# STORAGE.net
KiCad netlist of a schematic drawn in Altium Designer
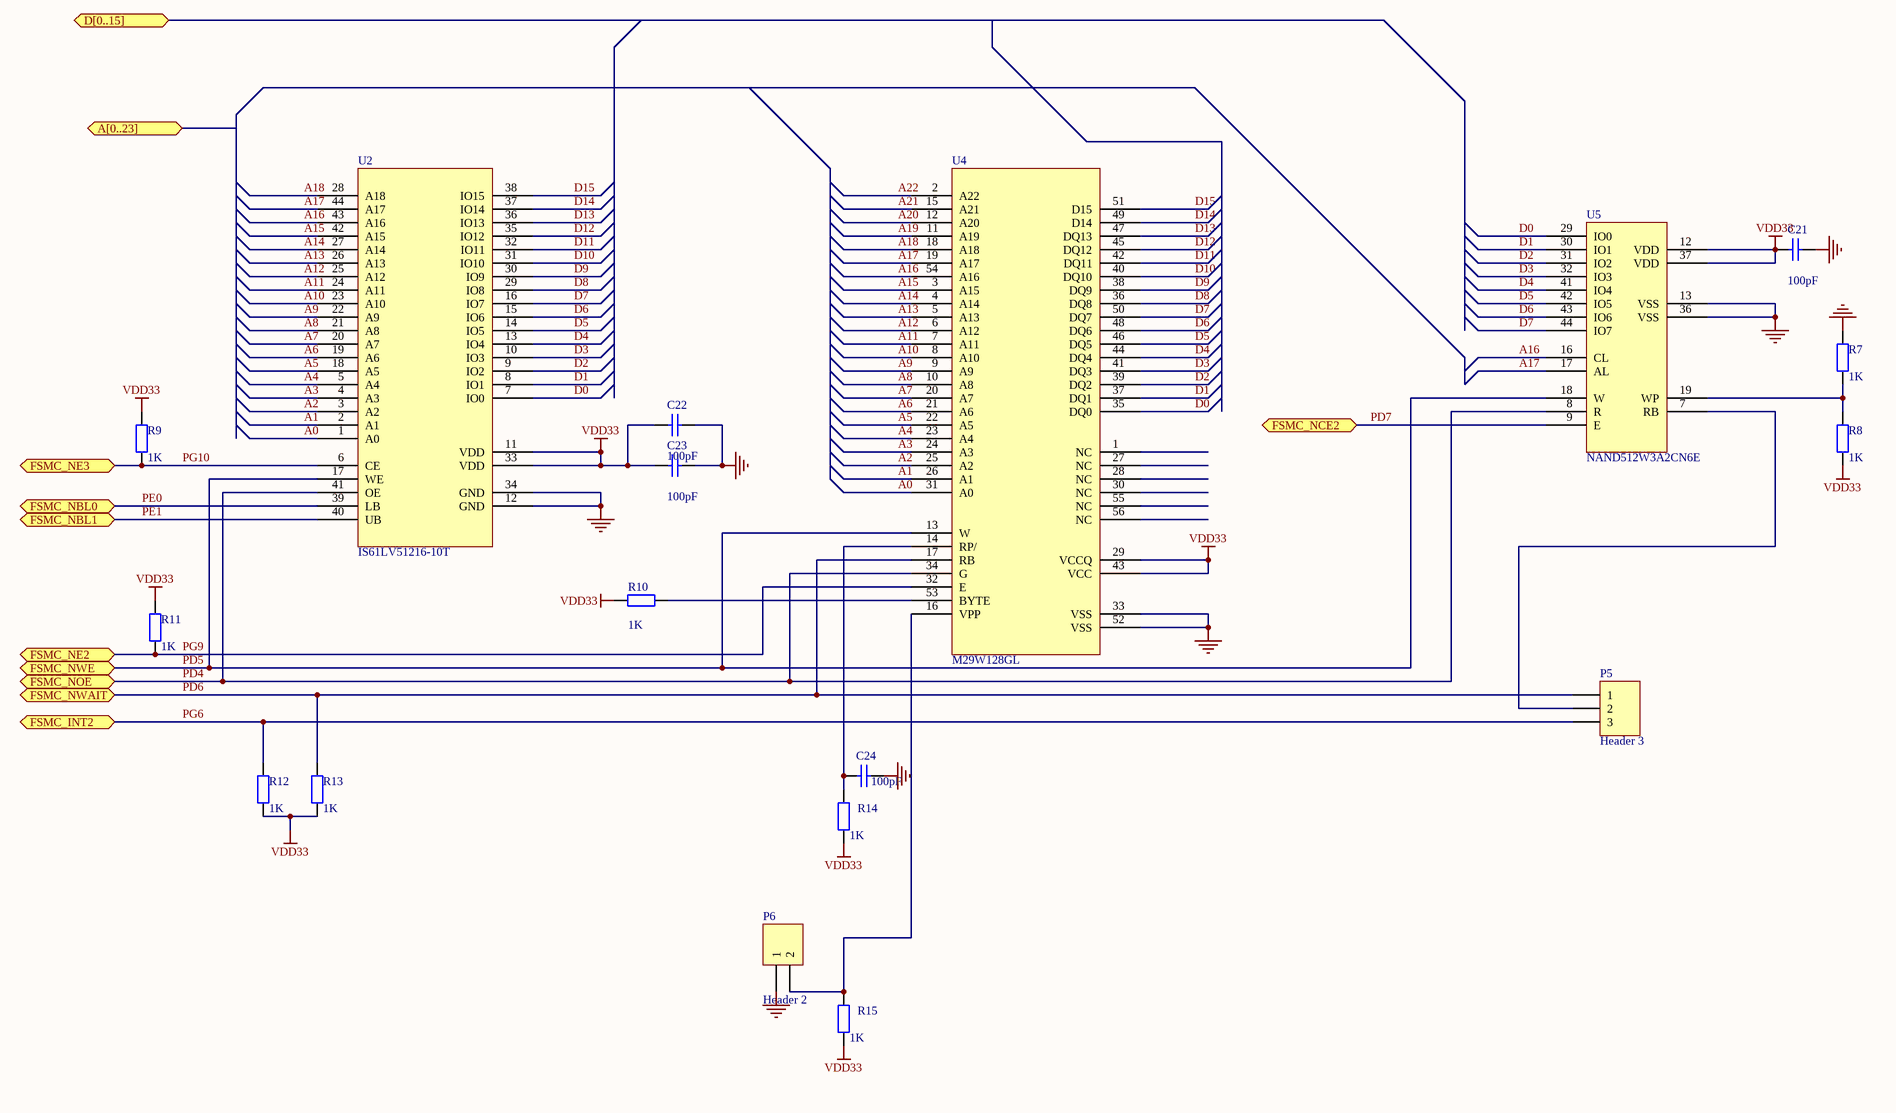
[diagram p0: STORAGE.SchDoc]

(export (version "E")
  (design (tool "Eeschema 10.0.6"))
  (components
    (comp (ref "C21")
      (value "100pF")
      (footprint "0805")
      (description "Capacitor")
      (fields (field (name "Comment") "Cap") (field (name "PUBLISHER") "Altium Limited"))
      (libsource (lib "Miscellaneous Devices") (part "Cap"))
    )
    (comp (ref "C22")
      (value "100pF")
      (footprint "0805")
      (description "Capacitor")
      (fields (field (name "Comment") "Cap") (field (name "PUBLISHER") "Altium Limited"))
      (libsource (lib "Miscellaneous Devices") (part "Cap"))
    )
    (comp (ref "C23")
      (value "100pF")
      (footprint "0805")
      (description "Capacitor")
      (fields (field (name "Comment") "Cap") (field (name "PUBLISHER") "Altium Limited"))
      (libsource (lib "Miscellaneous Devices") (part "Cap"))
    )
    (comp (ref "C24")
      (value "100pF")
      (footprint "0805")
      (description "Capacitor")
      (fields (field (name "Comment") "Cap") (field (name "PUBLISHER") "Altium Limited"))
      (libsource (lib "Miscellaneous Devices") (part "Cap"))
    )
    (comp (ref "P5")
      (value "Header 3")
      (footprint "HDR1X3")
      (description "Header, 3-Pin")
      (fields (field (name "PUBLISHER") "Altium Limited"))
      (libsource (lib "Miscellaneous Connectors") (part "Header 3"))
    )
    (comp (ref "P6")
      (value "Header 2")
      (footprint "HDR1X2")
      (description "Header, 2-Pin")
      (fields (field (name "PUBLISHER") "Altium Limited"))
      (libsource (lib "Miscellaneous Connectors") (part "Header 2"))
    )
    (comp (ref "R7")
      (value "1K")
      (footprint "0805")
      (description "Resistor")
      (fields (field (name "Comment") "Res2") (field (name "PUBLISHER") "Altium Limited"))
      (libsource (lib "") (part "Res2_2"))
    )
    (comp (ref "R8")
      (value "1K")
      (footprint "0805")
      (description "Resistor")
      (fields (field (name "Comment") "Res2") (field (name "PUBLISHER") "Altium Limited"))
      (libsource (lib "") (part "Res2_2"))
    )
    (comp (ref "R9")
      (value "1K")
      (footprint "0805")
      (description "Resistor")
      (fields (field (name "Comment") "Res2") (field (name "PUBLISHER") "Altium Limited"))
      (libsource (lib "") (part "Res2_2"))
    )
    (comp (ref "R10")
      (value "1K")
      (footprint "0805")
      (description "Resistor")
      (fields (field (name "Comment") "Res2") (field (name "PUBLISHER") "Altium Limited"))
      (libsource (lib "") (part "Res2_1"))
    )
    (comp (ref "R11")
      (value "1K")
      (footprint "0805")
      (description "Resistor")
      (fields (field (name "Comment") "Res2") (field (name "PUBLISHER") "Altium Limited"))
      (libsource (lib "") (part "Res2_2"))
    )
    (comp (ref "R12")
      (value "1K")
      (footprint "0805")
      (description "Resistor")
      (fields (field (name "Comment") "Res2") (field (name "PUBLISHER") "Altium Limited"))
      (libsource (lib "Miscellaneous Devices") (part "Res2"))
    )
    (comp (ref "R13")
      (value "1K")
      (footprint "0805")
      (description "Resistor")
      (fields (field (name "Comment") "Res2") (field (name "PUBLISHER") "Altium Limited"))
      (libsource (lib "") (part "Res2_2"))
    )
    (comp (ref "R14")
      (value "1K")
      (footprint "0805")
      (description "Resistor")
      (fields (field (name "Comment") "Res2") (field (name "PUBLISHER") "Altium Limited"))
      (libsource (lib "") (part "Res2_2"))
    )
    (comp (ref "R15")
      (value "1K")
      (footprint "0805")
      (description "Resistor")
      (fields (field (name "Comment") "Res2") (field (name "PUBLISHER") "Altium Limited"))
      (libsource (lib "") (part "Res2_2"))
    )
    (comp (ref "U2")
      (value "IS61LV51216-10T")
      (footprint "TSOP44")
      (libsource (lib "Schlib1") (part "IS61LV51216-10T"))
    )
    (comp (ref "U4") (value "M29W128GL") (footprint "TSOP56") (libsource (lib "Schlib1") (part "M29W128GL")))
    (comp (ref "U5")
      (value "NAND512W3A2CN6E")
      (footprint "TSOP48")
      (libsource (lib "Schlib1") (part "NAND512W3A2CN6E"))
    )
  )
  (nets
    (net (code "2") (name "/A0") (class "Default")
      (node (ref "U2") (pin "1") (pinfunction "A0_1") (pintype "passive"))
      (node (ref "U4") (pin "31") (pinfunction "A0_31") (pintype "passive"))
    )
    (net (code "3") (name "/A1") (class "Default")
      (node (ref "U2") (pin "2") (pinfunction "A1_2") (pintype "passive"))
      (node (ref "U4") (pin "26") (pinfunction "A1_26") (pintype "passive"))
    )
    (net (code "4") (name "/A2") (class "Default")
      (node (ref "U2") (pin "3") (pinfunction "A2_3") (pintype "passive"))
      (node (ref "U4") (pin "25") (pinfunction "A2_25") (pintype "passive"))
    )
    (net (code "5") (name "/A3") (class "Default")
      (node (ref "U2") (pin "4") (pinfunction "A3_4") (pintype "passive"))
      (node (ref "U4") (pin "24") (pinfunction "A3_24") (pintype "passive"))
    )
    (net (code "6") (name "/A4") (class "Default")
      (node (ref "U2") (pin "5") (pinfunction "A4_5") (pintype "passive"))
      (node (ref "U4") (pin "23") (pinfunction "A4_23") (pintype "passive"))
    )
    (net (code "7") (name "/A5") (class "Default")
      (node (ref "U2") (pin "18") (pinfunction "A5_18") (pintype "passive"))
      (node (ref "U4") (pin "22") (pinfunction "A5_22") (pintype "passive"))
    )
    (net (code "8") (name "/A6") (class "Default")
      (node (ref "U2") (pin "19") (pinfunction "A6_19") (pintype "passive"))
      (node (ref "U4") (pin "21") (pinfunction "A6_21") (pintype "passive"))
    )
    (net (code "9") (name "/A7") (class "Default")
      (node (ref "U2") (pin "20") (pinfunction "A7_20") (pintype "passive"))
      (node (ref "U4") (pin "20") (pinfunction "A7_20") (pintype "passive"))
    )
    (net (code "10") (name "/A8") (class "Default")
      (node (ref "U2") (pin "21") (pinfunction "A8_21") (pintype "passive"))
      (node (ref "U4") (pin "10") (pinfunction "A8_10") (pintype "passive"))
    )
    (net (code "11") (name "/A9") (class "Default")
      (node (ref "U2") (pin "22") (pinfunction "A9_22") (pintype "passive"))
      (node (ref "U4") (pin "9") (pinfunction "A9_9") (pintype "passive"))
    )
    (net (code "12") (name "/A10") (class "Default")
      (node (ref "U2") (pin "23") (pinfunction "A10_23") (pintype "passive"))
      (node (ref "U4") (pin "8") (pinfunction "A10_8") (pintype "passive"))
    )
    (net (code "13") (name "/A11") (class "Default")
      (node (ref "U2") (pin "24") (pinfunction "A11_24") (pintype "passive"))
      (node (ref "U4") (pin "7") (pinfunction "A11_7") (pintype "passive"))
    )
    (net (code "14") (name "/A12") (class "Default")
      (node (ref "U2") (pin "25") (pinfunction "A12_25") (pintype "passive"))
      (node (ref "U4") (pin "6") (pinfunction "A12_6") (pintype "passive"))
    )
    (net (code "15") (name "/A13") (class "Default")
      (node (ref "U2") (pin "26") (pinfunction "A13_26") (pintype "passive"))
      (node (ref "U4") (pin "5") (pinfunction "A13_5") (pintype "passive"))
    )
    (net (code "16") (name "/A14") (class "Default")
      (node (ref "U2") (pin "27") (pinfunction "A14_27") (pintype "passive"))
      (node (ref "U4") (pin "4") (pinfunction "A14_4") (pintype "passive"))
    )
    (net (code "17") (name "/A15") (class "Default")
      (node (ref "U2") (pin "42") (pinfunction "A15_42") (pintype "passive"))
      (node (ref "U4") (pin "3") (pinfunction "A15_3") (pintype "passive"))
    )
    (net (code "18") (name "/A16") (class "Default")
      (node (ref "U2") (pin "43") (pinfunction "A16_43") (pintype "passive"))
      (node (ref "U4") (pin "54") (pinfunction "A16_54") (pintype "passive"))
      (node (ref "U5") (pin "16") (pinfunction "CL_16") (pintype "passive"))
    )
    (net (code "19") (name "/A17") (class "Default")
      (node (ref "U2") (pin "44") (pinfunction "A17_44") (pintype "passive"))
      (node (ref "U4") (pin "19") (pinfunction "A17_19") (pintype "passive"))
      (node (ref "U5") (pin "17") (pinfunction "AL_17") (pintype "passive"))
    )
    (net (code "20") (name "/A18") (class "Default")
      (node (ref "U2") (pin "28") (pinfunction "A18_28") (pintype "passive"))
      (node (ref "U4") (pin "18") (pinfunction "A18_18") (pintype "passive"))
    )
    (net (code "21") (name "/A19") (class "Default")
      (node (ref "U4") (pin "11") (pinfunction "A19_11") (pintype "passive"))
    )
    (net (code "22") (name "/A20") (class "Default")
      (node (ref "U4") (pin "12") (pinfunction "A20_12") (pintype "passive"))
    )
    (net (code "23") (name "/A21") (class "Default")
      (node (ref "U4") (pin "15") (pinfunction "A21_15") (pintype "passive"))
    )
    (net (code "24") (name "/A22") (class "Default")
      (node (ref "U4") (pin "2") (pinfunction "A22_2") (pintype "passive"))
    )
    (net (code "26") (name "/D0") (class "Default")
      (node (ref "U2") (pin "7") (pinfunction "IO0_7") (pintype "passive"))
      (node (ref "U4") (pin "35") (pinfunction "DQ0_35") (pintype "passive"))
      (node (ref "U5") (pin "29") (pinfunction "IO0_29") (pintype "passive"))
    )
    (net (code "27") (name "/D1") (class "Default")
      (node (ref "U2") (pin "8") (pinfunction "IO1_8") (pintype "passive"))
      (node (ref "U4") (pin "37") (pinfunction "DQ1_37") (pintype "passive"))
      (node (ref "U5") (pin "30") (pinfunction "IO1_30") (pintype "passive"))
    )
    (net (code "28") (name "/D2") (class "Default")
      (node (ref "U2") (pin "9") (pinfunction "IO2_9") (pintype "passive"))
      (node (ref "U4") (pin "39") (pinfunction "DQ2_39") (pintype "passive"))
      (node (ref "U5") (pin "31") (pinfunction "IO2_31") (pintype "passive"))
    )
    (net (code "29") (name "/D3") (class "Default")
      (node (ref "U2") (pin "10") (pinfunction "IO3_10") (pintype "passive"))
      (node (ref "U4") (pin "41") (pinfunction "DQ3_41") (pintype "passive"))
      (node (ref "U5") (pin "32") (pinfunction "IO3_32") (pintype "passive"))
    )
    (net (code "30") (name "/D4") (class "Default")
      (node (ref "U2") (pin "13") (pinfunction "IO4_13") (pintype "passive"))
      (node (ref "U4") (pin "44") (pinfunction "DQ4_44") (pintype "passive"))
      (node (ref "U5") (pin "41") (pinfunction "IO4_41") (pintype "passive"))
    )
    (net (code "31") (name "/D5") (class "Default")
      (node (ref "U2") (pin "14") (pinfunction "IO5_14") (pintype "passive"))
      (node (ref "U4") (pin "46") (pinfunction "DQ5_46") (pintype "passive"))
      (node (ref "U5") (pin "42") (pinfunction "IO5_42") (pintype "passive"))
    )
    (net (code "32") (name "/D6") (class "Default")
      (node (ref "U2") (pin "15") (pinfunction "IO6_15") (pintype "passive"))
      (node (ref "U4") (pin "48") (pinfunction "DQ6_48") (pintype "passive"))
      (node (ref "U5") (pin "43") (pinfunction "IO6_43") (pintype "passive"))
    )
    (net (code "33") (name "/D7") (class "Default")
      (node (ref "U2") (pin "16") (pinfunction "IO7_16") (pintype "passive"))
      (node (ref "U4") (pin "50") (pinfunction "DQ7_50") (pintype "passive"))
      (node (ref "U5") (pin "44") (pinfunction "IO7_44") (pintype "passive"))
    )
    (net (code "34") (name "/D8") (class "Default")
      (node (ref "U2") (pin "29") (pinfunction "IO8_29") (pintype "passive"))
      (node (ref "U4") (pin "36") (pinfunction "DQ8_36") (pintype "passive"))
    )
    (net (code "35") (name "/D9") (class "Default")
      (node (ref "U2") (pin "30") (pinfunction "IO9_30") (pintype "passive"))
      (node (ref "U4") (pin "38") (pinfunction "DQ9_38") (pintype "passive"))
    )
    (net (code "36") (name "/D10") (class "Default")
      (node (ref "U2") (pin "31") (pinfunction "IO10_31") (pintype "passive"))
      (node (ref "U4") (pin "40") (pinfunction "DQ10_40") (pintype "passive"))
    )
    (net (code "37") (name "/D11") (class "Default")
      (node (ref "U2") (pin "32") (pinfunction "IO11_32") (pintype "passive"))
      (node (ref "U4") (pin "42") (pinfunction "DQ11_42") (pintype "passive"))
    )
    (net (code "38") (name "/D12") (class "Default")
      (node (ref "U2") (pin "35") (pinfunction "IO12_35") (pintype "passive"))
      (node (ref "U4") (pin "45") (pinfunction "DQ12_45") (pintype "passive"))
    )
    (net (code "39") (name "/D13") (class "Default")
      (node (ref "U2") (pin "36") (pinfunction "IO13_36") (pintype "passive"))
      (node (ref "U4") (pin "47") (pinfunction "DQ13_47") (pintype "passive"))
    )
    (net (code "40") (name "/D14") (class "Default")
      (node (ref "U2") (pin "37") (pinfunction "IO14_37") (pintype "passive"))
      (node (ref "U4") (pin "49") (pinfunction "D14_49") (pintype "passive"))
    )
    (net (code "41") (name "/D15") (class "Default")
      (node (ref "U2") (pin "38") (pinfunction "IO15_38") (pintype "passive"))
      (node (ref "U4") (pin "51") (pinfunction "D15_51") (pintype "passive"))
    )
    (net (code "43") (name "/PD4") (class "Default")
      (node (ref "U2") (pin "41") (pinfunction "OE_41") (pintype "passive"))
      (node (ref "U4") (pin "34") (pinfunction "G_34") (pintype "passive"))
      (node (ref "U5") (pin "8") (pinfunction "R_8") (pintype "passive"))
    )
    (net (code "44") (name "/PD5") (class "Default")
      (node (ref "U2") (pin "17") (pinfunction "WE_17") (pintype "passive"))
      (node (ref "U4") (pin "13") (pinfunction "W_13") (pintype "passive"))
      (node (ref "U5") (pin "18") (pinfunction "W_18") (pintype "passive"))
    )
    (net (code "45") (name "/PD6") (class "Default")
      (node (ref "P5") (pin "1") (pinfunction "1_1") (pintype "passive"))
      (node (ref "R13") (pin "2") (pinfunction "2_2") (pintype "passive"))
      (node (ref "U4") (pin "17") (pinfunction "RB_17") (pintype "passive"))
    )
    (net (code "46") (name "/PD7") (class "Default")
      (node (ref "U5") (pin "9") (pinfunction "E_9") (pintype "passive"))
    )
    (net (code "47") (name "/PE0") (class "Default")
      (node (ref "U2") (pin "39") (pinfunction "LB_39") (pintype "passive"))
    )
    (net (code "48") (name "/PE1") (class "Default")
      (node (ref "U2") (pin "40") (pinfunction "UB_40") (pintype "passive"))
    )
    (net (code "49") (name "/PG6") (class "Default")
      (node (ref "P5") (pin "3") (pinfunction "3_3") (pintype "passive"))
      (node (ref "R12") (pin "1") (pinfunction "1_1") (pintype "passive"))
    )
    (net (code "50") (name "/PG9") (class "Default")
      (node (ref "R11") (pin "1") (pinfunction "1_1") (pintype "passive"))
      (node (ref "U4") (pin "32") (pinfunction "E_32") (pintype "passive"))
    )
    (net (code "51") (name "/PG10") (class "Default")
      (node (ref "R9") (pin "1") (pinfunction "1_1") (pintype "passive"))
      (node (ref "U2") (pin "6") (pinfunction "CE_6") (pintype "passive"))
    )
    (net (code "52") (name "GND") (class "Default")
      (node (ref "C21") (pin "2") (pinfunction "2_2") (pintype "passive"))
      (node (ref "C22") (pin "2") (pinfunction "2_2") (pintype "passive"))
      (node (ref "C23") (pin "2") (pinfunction "2_2") (pintype "passive"))
      (node (ref "C24") (pin "2") (pinfunction "2_2") (pintype "passive"))
      (node (ref "P6") (pin "1") (pinfunction "1_1") (pintype "passive"))
      (node (ref "R7") (pin "2") (pinfunction "2_2") (pintype "passive"))
      (node (ref "U2") (pin "12") (pinfunction "GND_12") (pintype "passive"))
      (node (ref "U2") (pin "34") (pinfunction "GND_34") (pintype "passive"))
      (node (ref "U4") (pin "33") (pinfunction "VSS_33") (pintype "passive"))
      (node (ref "U4") (pin "52") (pinfunction "VSS_52") (pintype "passive"))
      (node (ref "U5") (pin "13") (pinfunction "VSS_13") (pintype "passive"))
      (node (ref "U5") (pin "36") (pinfunction "VSS_36") (pintype "passive"))
    )
    (net (code "53") (name "Net-(U4-BYTE)") (class "Default")
      (node (ref "R10") (pin "1") (pinfunction "1_1") (pintype "passive"))
      (node (ref "U4") (pin "53") (pinfunction "BYTE_53") (pintype "passive"))
    )
    (net (code "54") (name "Net-(U4-RP{slash})") (class "Default")
      (node (ref "C24") (pin "1") (pinfunction "1_1") (pintype "passive"))
      (node (ref "R14") (pin "2") (pinfunction "2_2") (pintype "passive"))
      (node (ref "U4") (pin "14") (pinfunction "RP/_14") (pintype "passive"))
    )
    (net (code "55") (name "Net-(U4-VPP)") (class "Default")
      (node (ref "P6") (pin "2") (pinfunction "2_2") (pintype "passive"))
      (node (ref "R15") (pin "2") (pinfunction "2_2") (pintype "passive"))
      (node (ref "U4") (pin "16") (pinfunction "VPP_16") (pintype "passive"))
    )
    (net (code "56") (name "Net-(U5-RB)") (class "Default")
      (node (ref "P5") (pin "2") (pinfunction "2_2") (pintype "passive"))
      (node (ref "U5") (pin "7") (pinfunction "RB_7") (pintype "passive"))
    )
    (net (code "57") (name "Net-(U5-WP)") (class "Default")
      (node (ref "R7") (pin "1") (pinfunction "1_1") (pintype "passive"))
      (node (ref "R8") (pin "2") (pinfunction "2_2") (pintype "passive"))
      (node (ref "U5") (pin "19") (pinfunction "WP_19") (pintype "passive"))
    )
    (net (code "58") (name "VDD33") (class "Default")
      (node (ref "C21") (pin "1") (pinfunction "1_1") (pintype "passive"))
      (node (ref "C22") (pin "1") (pinfunction "1_1") (pintype "passive"))
      (node (ref "C23") (pin "1") (pinfunction "1_1") (pintype "passive"))
      (node (ref "R10") (pin "2") (pinfunction "2_2") (pintype "passive"))
      (node (ref "R11") (pin "2") (pinfunction "2_2") (pintype "passive"))
      (node (ref "R12") (pin "2") (pinfunction "2_2") (pintype "passive"))
      (node (ref "R13") (pin "1") (pinfunction "1_1") (pintype "passive"))
      (node (ref "R14") (pin "1") (pinfunction "1_1") (pintype "passive"))
      (node (ref "R15") (pin "1") (pinfunction "1_1") (pintype "passive"))
      (node (ref "R8") (pin "1") (pinfunction "1_1") (pintype "passive"))
      (node (ref "R9") (pin "2") (pinfunction "2_2") (pintype "passive"))
      (node (ref "U2") (pin "11") (pinfunction "VDD_11") (pintype "passive"))
      (node (ref "U2") (pin "33") (pinfunction "VDD_33") (pintype "passive"))
      (node (ref "U4") (pin "29") (pinfunction "VCCQ_29") (pintype "passive"))
      (node (ref "U4") (pin "43") (pinfunction "VCC_43") (pintype "passive"))
      (node (ref "U5") (pin "12") (pinfunction "VDD_12") (pintype "passive"))
      (node (ref "U5") (pin "37") (pinfunction "VDD_37") (pintype "passive"))
    )
    (net (code "59") (name "unconnected-(U4-NC-Pad1)") (class "Default")
      (node (ref "U4") (pin "1") (pinfunction "NC_1") (pintype "passive"))
    )
    (net (code "60") (name "unconnected-(U4-NC-Pad27)") (class "Default")
      (node (ref "U4") (pin "27") (pinfunction "NC_27") (pintype "passive"))
    )
    (net (code "61") (name "unconnected-(U4-NC-Pad28)") (class "Default")
      (node (ref "U4") (pin "28") (pinfunction "NC_28") (pintype "passive"))
    )
    (net (code "62") (name "unconnected-(U4-NC-Pad30)") (class "Default")
      (node (ref "U4") (pin "30") (pinfunction "NC_30") (pintype "passive"))
    )
    (net (code "63") (name "unconnected-(U4-NC-Pad55)") (class "Default")
      (node (ref "U4") (pin "55") (pinfunction "NC_55") (pintype "passive"))
    )
    (net (code "64") (name "unconnected-(U4-NC-Pad56)") (class "Default")
      (node (ref "U4") (pin "56") (pinfunction "NC_56") (pintype "passive"))
    )
  )
)
